# Adder.net
KiCad netlist of a schematic drawn in Altium Designer
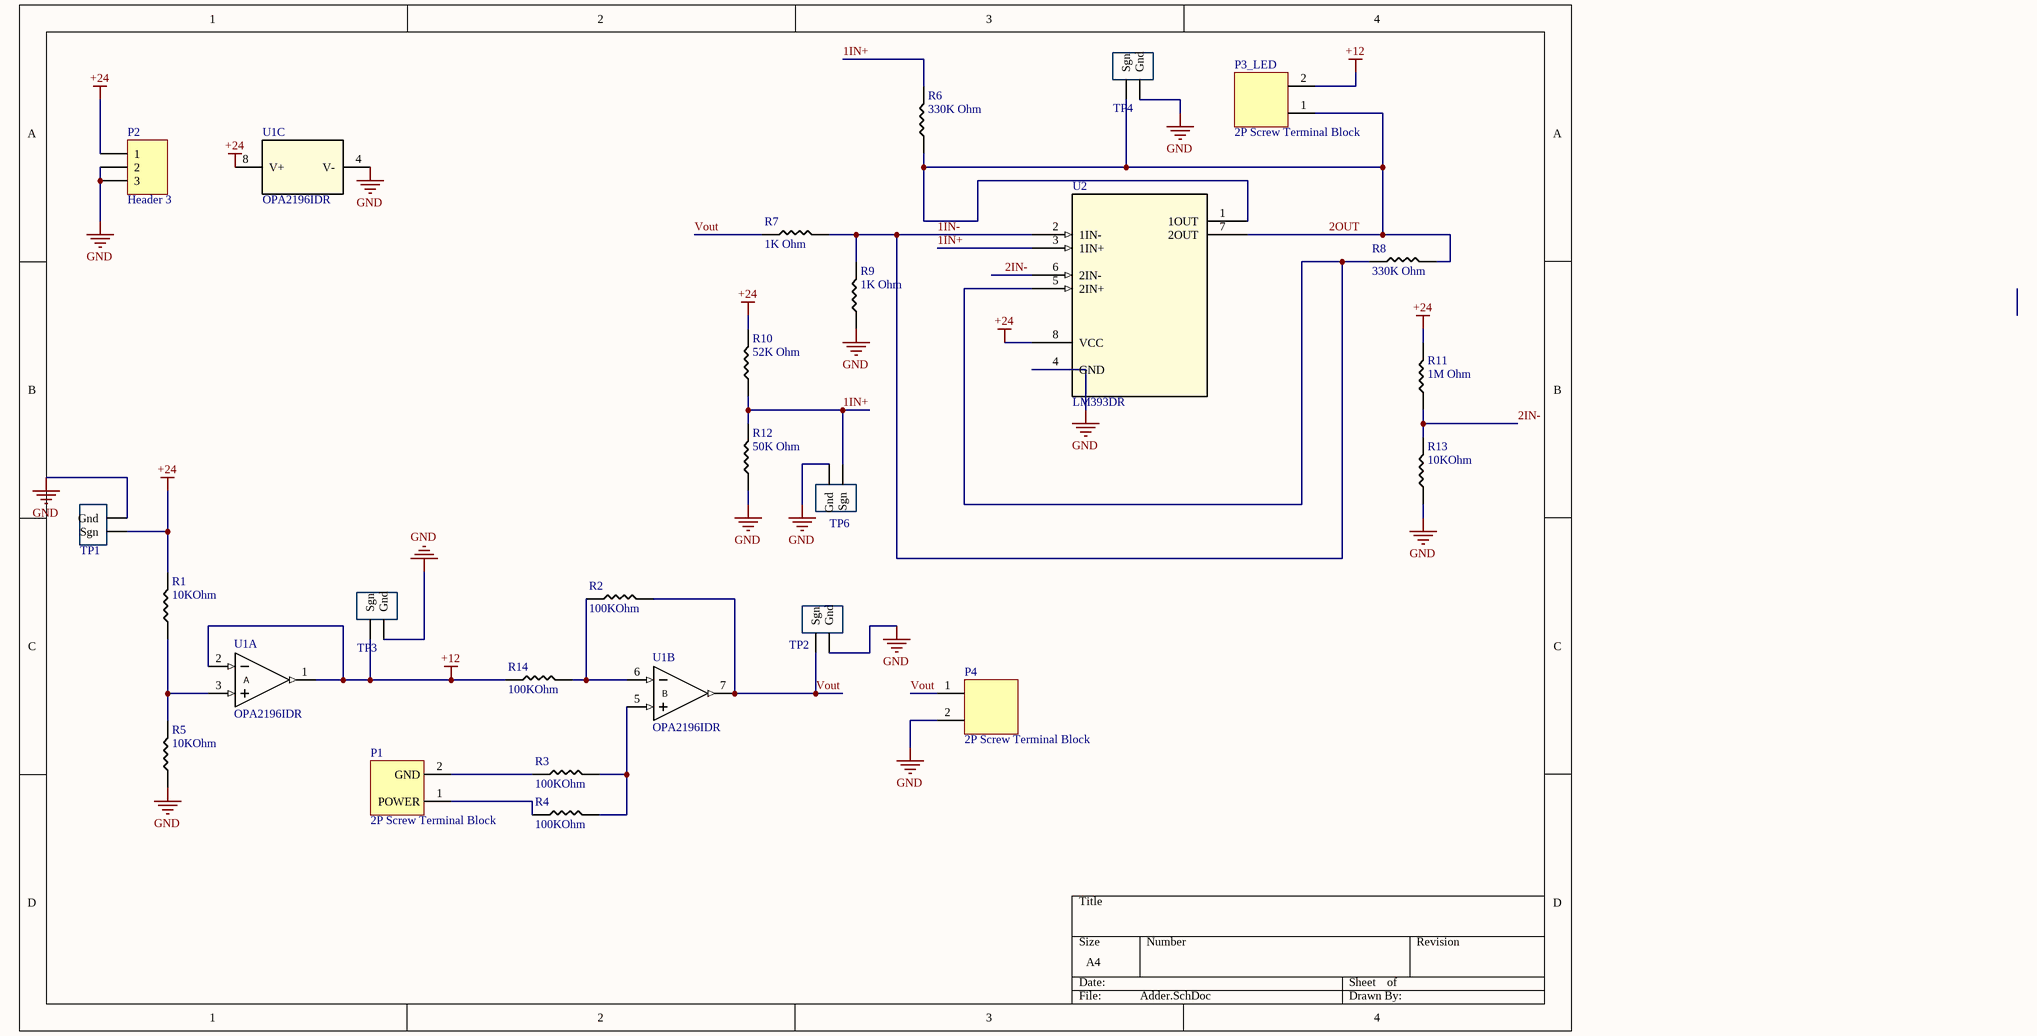
[diagram p0: Adder.SchDoc]

(export (version "E")
  (design (tool "Eeschema 10.0.6"))
  (components
    (comp (ref "P1")
      (value "2P Screw Terminal Block")
      (footprint "P_Terminal block 3.5mm-pitch")
      (description "Green Straight pin 3.5mm  pitch; P=3.5mm  Screw terminal ROHS")
      (fields (field (name "MFR PART #") "KF350-3.5-2P") (field (name "MANUFACTURER") "Cixi Kefa Elec"))
      (libsource (lib "") (part "P_Terminal block_1"))
    )
    (comp (ref "P2")
      (value "Header 3")
      (footprint "HDR1X3")
      (description "Header, 3-Pin")
      (fields (field (name "PUBLISHER") "Altium Limited"))
      (libsource (lib "Miscellaneous Connectors") (part "Header 3"))
    )
    (comp (ref "P3_LED")
      (value "2P Screw Terminal Block")
      (footprint "P_Terminal block 3.5mm-pitch")
      (description "Green Straight pin 3.5mm  pitch; P=3.5mm  Screw terminal ROHS")
      (fields (field (name "MFR PART #") "KF350-3.5-2P") (field (name "MANUFACTURER") "Cixi Kefa Elec"))
      (libsource (lib "") (part "P_Terminal block_2"))
    )
    (comp (ref "P4")
      (value "2P Screw Terminal Block")
      (footprint "P_Terminal block 3.5mm-pitch")
      (description "Green Straight pin 3.5mm  pitch; P=3.5mm  Screw terminal ROHS")
      (fields (field (name "MFR PART #") "KF350-3.5-2P") (field (name "MANUFACTURER") "Cixi Kefa Elec"))
      (libsource (lib "ECEN5730Lib_2023_05_DS") (part "P_Terminal block"))
    )
    (comp (ref "R1")
      (value "10KOhm")
      (footprint "1206_Passive_Resitor")
      (description "10 kOhms ±5% 0.25W, 1/4W Chip Resistor 1206 (3216 Metric) Automotive AEC-Q200 Thick Film")
      (fields (field (name "MFR PART #") "RMCF1206FT10K0") (field (name "LCSC PART#") "C17902"))
      (libsource (lib "ECEN5730Lib_2023_05_DS") (part "R_10KOhm_1206"))
    )
    (comp (ref "R2")
      (value "100KOhm")
      (footprint "1206_Passive_Resitor")
      (description "100kΩ ±1% 0.25W ±100ppm/℃ 1206 Chip Resistor - Surface Mount RoHS")
      (fields (field (name "LCSC PART#") "C17900") (field (name "MFR PART #") "1206W4F1003T5E"))
      (libsource (lib "ECEN5730Lib_2023_05_DS") (part "R_100KOhm_1206"))
    )
    (comp (ref "R3")
      (value "100KOhm")
      (footprint "1206_Passive_Resitor")
      (description "100kΩ ±1% 0.25W ±100ppm/℃ 1206 Chip Resistor - Surface Mount RoHS")
      (fields (field (name "LCSC PART#") "C17900") (field (name "MFR PART #") "1206W4F1003T5E"))
      (libsource (lib "ECEN5730Lib_2023_05_DS") (part "R_100KOhm_1206"))
    )
    (comp (ref "R4")
      (value "100KOhm")
      (footprint "1206_Passive_Resitor")
      (description "100kΩ ±1% 0.25W ±100ppm/℃ 1206 Chip Resistor - Surface Mount RoHS")
      (fields (field (name "LCSC PART#") "C17900") (field (name "MFR PART #") "1206W4F1003T5E"))
      (libsource (lib "ECEN5730Lib_2023_05_DS") (part "R_100KOhm_1206"))
    )
    (comp (ref "R5")
      (value "10KOhm")
      (footprint "1206_Passive_Resitor")
      (description "10 kOhms ±5% 0.25W, 1/4W Chip Resistor 1206 (3216 Metric) Automotive AEC-Q200 Thick Film")
      (fields (field (name "MFR PART #") "RMCF1206FT10K0") (field (name "LCSC PART#") "C17902"))
      (libsource (lib "ECEN5730Lib_2023_05_DS") (part "R_10KOhm_1206"))
    )
    (comp (ref "R6")
      (value "330K Ohm")
      (footprint "1206_Passive_Resitor")
      (description "CHIP RESISTOR - SURFACE MOUNT 1KOHMS ±1% 1/4W 1206 ROHS")
      (fields (field (name "MFR PART #") "RNCP1206FTD1K00CT") (field (name "LCSC PART#") "C4410"))
      (libsource (lib "ECEN5730Lib_2023_05_DS") (part "R_1K_1206"))
    )
    (comp (ref "R7")
      (value "1K Ohm")
      (footprint "1206_Passive_Resitor")
      (description "CHIP RESISTOR - SURFACE MOUNT 1KOHMS ±1% 1/4W 1206 ROHS")
      (fields (field (name "MFR PART #") "RNCP1206FTD1K00CT") (field (name "LCSC PART#") "C4410"))
      (libsource (lib "ECEN5730Lib_2023_05_DS") (part "R_1K_1206"))
    )
    (comp (ref "R8")
      (value "330K Ohm")
      (footprint "1206_Passive_Resitor")
      (description "CHIP RESISTOR - SURFACE MOUNT 1KOHMS ±1% 1/4W 1206 ROHS")
      (fields (field (name "MFR PART #") "RNCP1206FTD1K00CT") (field (name "LCSC PART#") "C4410"))
      (libsource (lib "ECEN5730Lib_2023_05_DS") (part "R_1K_1206"))
    )
    (comp (ref "R9")
      (value "1K Ohm")
      (footprint "1206_Passive_Resitor")
      (description "CHIP RESISTOR - SURFACE MOUNT 1KOHMS ±1% 1/4W 1206 ROHS")
      (fields (field (name "MFR PART #") "RNCP1206FTD1K00CT") (field (name "LCSC PART#") "C4410"))
      (libsource (lib "ECEN5730Lib_2023_05_DS") (part "R_1K_1206"))
    )
    (comp (ref "R10")
      (value "52K Ohm")
      (footprint "1206_Passive_Resitor")
      (description "CHIP RESISTOR - SURFACE MOUNT 52KOHMS ±1% 1/4W 1206 ROHS")
      (fields (field (name "MFR PART #") "RNCP1206FTD1K00CT") (field (name "LCSC PART#") "C4410"))
      (libsource (lib "ECEN5730Lib_2023_05_DS") (part "R_1K_1206"))
    )
    (comp (ref "R11")
      (value "1M Ohm")
      (footprint "1206_Passive_Resitor")
      (description "CHIP RESISTOR - SURFACE MOUNT 1MOHMS ±1% 1/4W 1206 ROHS")
      (fields (field (name "MFR PART #") "RMCF1206JT1M00") (field (name "LCSC PART#") "C17927"))
      (libsource (lib "ECEN5730Lib_2023_05_DS") (part "R_1M_1206"))
    )
    (comp (ref "R12")
      (value "50K Ohm")
      (footprint "1206_Passive_Resitor")
      (description "CHIP RESISTOR - SURFACE MOUNT 1KOHMS ±1% 1/4W 1206 ROHS")
      (fields (field (name "MFR PART #") "RNCP1206FTD1K00CT") (field (name "LCSC PART#") "C4410"))
      (libsource (lib "ECEN5730Lib_2023_05_DS") (part "R_1K_1206"))
    )
    (comp (ref "R13")
      (value "10KOhm")
      (footprint "1206_Passive_Resitor")
      (description "10 kOhms ±5% 0.25W, 1/4W Chip Resistor 1206 (3216 Metric) Automotive AEC-Q200 Thick Film")
      (fields (field (name "MFR PART #") "RMCF1206FT10K0") (field (name "LCSC PART#") "C17902"))
      (libsource (lib "ECEN5730Lib_2023_05_DS") (part "R_10KOhm_1206"))
    )
    (comp (ref "R14")
      (value "100KOhm")
      (footprint "1206_Passive_Resitor")
      (description "100kΩ ±1% 0.25W ±100ppm/℃ 1206 Chip Resistor - Surface Mount RoHS")
      (fields (field (name "LCSC PART#") "C17900") (field (name "MFR PART #") "1206W4F1003T5E"))
      (libsource (lib "ECEN5730Lib_2023_05_DS") (part "R_100KOhm_1206"))
    )
    (comp (ref "TP1")
      (value "10x Probe TP")
      (footprint "TP10x_Probe")
      (description "Test Point 300 mil centers")
      (libsource (lib "") (part "TP_10x_Probe_1"))
    )
    (comp (ref "TP2")
      (value "10x Probe TP")
      (footprint "TP10x_Probe")
      (description "Test Point 300 mil centers")
      (libsource (lib "ECEN5730Lib_2023_05_DS") (part "TP_10x_Probe"))
    )
    (comp (ref "TP3")
      (value "10x Probe TP")
      (footprint "TP10x_Probe")
      (description "Test Point 300 mil centers")
      (libsource (lib "ECEN5730Lib_2023_05_DS") (part "TP_10x_Probe"))
    )
    (comp (ref "TP4")
      (value "10x Probe TP")
      (footprint "TP10x_Probe")
      (description "Test Point 300 mil centers")
      (libsource (lib "ECEN5730Lib_2023_05_DS") (part "TP_10x_Probe"))
    )
    (comp (ref "TP6")
      (value "10x Probe TP")
      (footprint "TP10x_Probe")
      (description "Test Point 300 mil centers")
      (libsource (lib "") (part "TP_10x_Probe_2"))
    )
    (comp (ref "U1")
      (value "OPA2196IDR")
      (footprint "D0008A_N")
      (description "Dual, 36-V, low power, all-purpose amplifier with mux-friendly input 8-SOIC -40 to 125")
      (fields (field (name "COPYRIGHT") "Copyright (C) 2026 Ultra Librarian. All rights reserved."))
      (libsource (lib "Integrated_Library1") (part "OPA2196IDR"))
    )
    (comp (ref "U2")
      (value "LM393DR")
      (footprint "D8")
      (description "Dual differential comparator, commercial grade 8-SOIC 0 to 70")
      (fields (field (name "COPYRIGHT") "Copyright (C) 2025 Ultra Librarian. All rights reserved."))
      (libsource (lib "LM393DR") (part "LM393DR"))
    )
  )
  (nets
    (net (code "1") (name "+12") (class "Default")
      (node (ref "P3_LED") (pin "2") (pinfunction "GND_2") (pintype "passive"))
      (node (ref "R14") (pin "1") (pinfunction "1_1") (pintype "passive"))
      (node (ref "TP3") (pin "1") (pinfunction "Sgn_1") (pintype "passive"))
      (node (ref "U1") (pin "1") (pinfunction "OUT_1") (pintype "output"))
      (node (ref "U1") (pin "2") (pinfunction "IN-_2") (pintype "input"))
    )
    (net (code "2") (name "+24") (class "Default")
      (node (ref "P2") (pin "1") (pinfunction "1_1") (pintype "passive"))
      (node (ref "R1") (pin "2") (pinfunction "2_2") (pintype "passive"))
      (node (ref "R10") (pin "2") (pinfunction "2_2") (pintype "passive"))
      (node (ref "R11") (pin "2") (pinfunction "2_2") (pintype "passive"))
      (node (ref "TP1") (pin "1") (pinfunction "Sgn_1") (pintype "passive"))
      (node (ref "U1") (pin "8") (pinfunction "V+_8") (pintype "power_in"))
      (node (ref "U2") (pin "8") (pinfunction "VCC_8") (pintype "power_in"))
    )
    (net (code "3") (name "/1IN+") (class "Default")
      (node (ref "R10") (pin "1") (pinfunction "1_1") (pintype "passive"))
      (node (ref "R12") (pin "2") (pinfunction "2_2") (pintype "passive"))
      (node (ref "R6") (pin "2") (pinfunction "2_2") (pintype "passive"))
      (node (ref "TP6") (pin "1") (pinfunction "Sgn_1") (pintype "passive"))
      (node (ref "U2") (pin "3") (pinfunction "1IN+_3") (pintype "input"))
    )
    (net (code "4") (name "/1IN-") (class "Default")
      (node (ref "R7") (pin "2") (pinfunction "2_2") (pintype "passive"))
      (node (ref "R8") (pin "1") (pinfunction "1_1") (pintype "passive"))
      (node (ref "R9") (pin "2") (pinfunction "2_2") (pintype "passive"))
      (node (ref "U2") (pin "2") (pinfunction "1IN-_2") (pintype "input"))
      (node (ref "U2") (pin "5") (pinfunction "2IN+_5") (pintype "input"))
    )
    (net (code "5") (name "/2IN-") (class "Default")
      (node (ref "R11") (pin "1") (pinfunction "1_1") (pintype "passive"))
      (node (ref "R13") (pin "2") (pinfunction "2_2") (pintype "passive"))
      (node (ref "U2") (pin "6") (pinfunction "2IN-_6") (pintype "input"))
    )
    (net (code "6") (name "/2OUT") (class "Default")
      (node (ref "P3_LED") (pin "1") (pinfunction "POWER_1") (pintype "passive"))
      (node (ref "R6") (pin "1") (pinfunction "1_1") (pintype "passive"))
      (node (ref "R8") (pin "2") (pinfunction "2_2") (pintype "passive"))
      (node (ref "TP4") (pin "1") (pinfunction "Sgn_1") (pintype "passive"))
      (node (ref "U2") (pin "1") (pinfunction "1OUT_1") (pintype "passive"))
      (node (ref "U2") (pin "7") (pinfunction "2OUT_7") (pintype "passive"))
    )
    (net (code "8") (name "/Vout") (class "Default")
      (node (ref "P4") (pin "1") (pinfunction "POWER_1") (pintype "passive"))
      (node (ref "R2") (pin "2") (pinfunction "2_2") (pintype "passive"))
      (node (ref "R7") (pin "1") (pinfunction "1_1") (pintype "passive"))
      (node (ref "TP2") (pin "1") (pinfunction "Sgn_1") (pintype "passive"))
      (node (ref "U1") (pin "7") (pinfunction "OUT_7") (pintype "output"))
    )
    (net (code "9") (name "GND") (class "Default")
      (node (ref "P2") (pin "2") (pinfunction "2_2") (pintype "passive"))
      (node (ref "P2") (pin "3") (pinfunction "3_3") (pintype "passive"))
      (node (ref "P4") (pin "2") (pinfunction "GND_2") (pintype "passive"))
      (node (ref "R12") (pin "1") (pinfunction "1_1") (pintype "passive"))
      (node (ref "R13") (pin "1") (pinfunction "1_1") (pintype "passive"))
      (node (ref "R5") (pin "1") (pinfunction "1_1") (pintype "passive"))
      (node (ref "R9") (pin "1") (pinfunction "1_1") (pintype "passive"))
      (node (ref "TP1") (pin "2") (pinfunction "Gnd_2") (pintype "passive"))
      (node (ref "TP2") (pin "2") (pinfunction "Gnd_2") (pintype "passive"))
      (node (ref "TP3") (pin "2") (pinfunction "Gnd_2") (pintype "passive"))
      (node (ref "TP4") (pin "2") (pinfunction "Gnd_2") (pintype "passive"))
      (node (ref "TP6") (pin "2") (pinfunction "Gnd_2") (pintype "passive"))
      (node (ref "U1") (pin "4") (pinfunction "V-_4") (pintype "power_in"))
      (node (ref "U2") (pin "4") (pinfunction "GND_4") (pintype "power_in"))
    )
    (net (code "10") (name "Net-(P1-GND)") (class "Default")
      (node (ref "P1") (pin "2") (pinfunction "GND_2") (pintype "passive"))
      (node (ref "R3") (pin "1") (pinfunction "1_1") (pintype "passive"))
    )
    (net (code "11") (name "Net-(P1-POWER)") (class "Default")
      (node (ref "P1") (pin "1") (pinfunction "POWER_1") (pintype "passive"))
      (node (ref "R4") (pin "1") (pinfunction "1_1") (pintype "passive"))
    )
    (net (code "12") (name "Net-(U1A-IN+)") (class "Default")
      (node (ref "R1") (pin "1") (pinfunction "1_1") (pintype "passive"))
      (node (ref "R5") (pin "2") (pinfunction "2_2") (pintype "passive"))
      (node (ref "U1") (pin "3") (pinfunction "IN+_3") (pintype "input"))
    )
    (net (code "13") (name "Net-(U1B-IN+)") (class "Default")
      (node (ref "R3") (pin "2") (pinfunction "2_2") (pintype "passive"))
      (node (ref "R4") (pin "2") (pinfunction "2_2") (pintype "passive"))
      (node (ref "U1") (pin "5") (pinfunction "IN+_5") (pintype "input"))
    )
    (net (code "14") (name "Net-(U1B-IN-)") (class "Default")
      (node (ref "R14") (pin "2") (pinfunction "2_2") (pintype "passive"))
      (node (ref "R2") (pin "1") (pinfunction "1_1") (pintype "passive"))
      (node (ref "U1") (pin "6") (pinfunction "IN-_6") (pintype "input"))
    )
  )
)
